# lcd_ex_cap_touch.net
KiCad netlist of a schematic drawn in Altium Designer
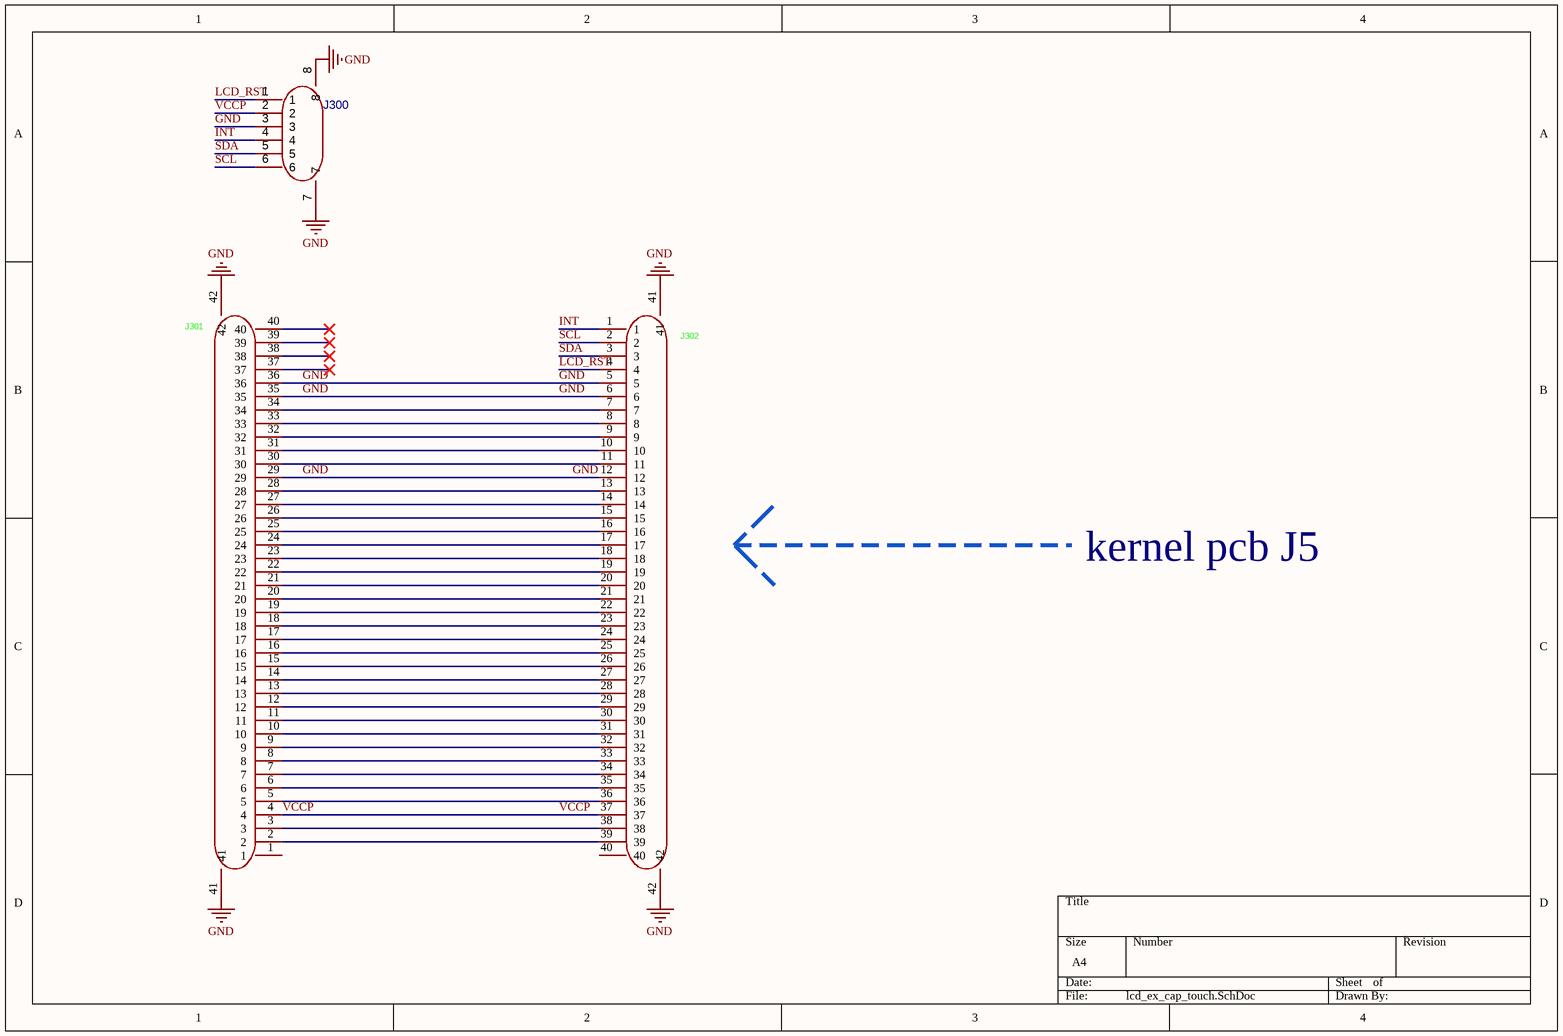
[diagram p0: lcd_ex_cap_touch.SchDoc]

(export (version "E")
  (design (tool "Eeschema 10.0.6"))
  (components
    (comp (ref "J300")
      (value "~")
      (footprint "FPC-SMD_P0.50-6P_QCHF-SM-H2.0_1")
      (libsource (lib "lcd_ex") (part "AFC24-S06FIA-00"))
    )
    (comp (ref "J301")
      (value "AFC01-S40FCA-00")
      (footprint "FPC-SMD_AFC01-S40FCA-00")
      (description "FPC")
      (fields (field (name "MANUFACTURER") "JS(钜硕电子)"))
      (libsource (lib "kernel") (part "AFC01-S40FCA-00"))
    )
    (comp (ref "J302")
      (value "AFC01-S40FCA-00")
      (footprint "FPC-SMD_AFC01-S40FCA-00")
      (description "FPC")
      (fields (field (name "MANUFACTURER") "JS(钜硕电子)"))
      (libsource (lib "kernel") (part "AFC01-S40FCA-00"))
    )
  )
  (nets
    (net (code "1") (name "/INT") (class "Default")
      (node (ref "J300") (pin "4") (pinfunction "4_4") (pintype "passive"))
      (node (ref "J302") (pin "1") (pinfunction "1_1") (pintype "passive"))
    )
    (net (code "2") (name "/LCD_RST") (class "Default")
      (node (ref "J300") (pin "1") (pinfunction "1_1") (pintype "passive"))
      (node (ref "J302") (pin "4") (pinfunction "4_4") (pintype "passive"))
    )
    (net (code "3") (name "/SCL") (class "Default")
      (node (ref "J300") (pin "6") (pinfunction "6_6") (pintype "passive"))
      (node (ref "J302") (pin "2") (pinfunction "2_2") (pintype "passive"))
    )
    (net (code "4") (name "/SDA") (class "Default")
      (node (ref "J300") (pin "5") (pinfunction "5_5") (pintype "passive"))
      (node (ref "J302") (pin "3") (pinfunction "3_3") (pintype "passive"))
    )
    (net (code "5") (name "/VCCP") (class "Default")
      (node (ref "J300") (pin "2") (pinfunction "2_2") (pintype "passive"))
      (node (ref "J301") (pin "4") (pinfunction "4_4") (pintype "passive"))
      (node (ref "J302") (pin "37") (pinfunction "37_37") (pintype "passive"))
    )
    (net (code "6") (name "GND") (class "Default")
      (node (ref "J300") (pin "3") (pinfunction "3_3") (pintype "passive"))
      (node (ref "J300") (pin "7") (pinfunction "7_7") (pintype "passive"))
      (node (ref "J300") (pin "8") (pinfunction "8_8") (pintype "passive"))
      (node (ref "J301") (pin "29") (pinfunction "29_29") (pintype "passive"))
      (node (ref "J301") (pin "35") (pinfunction "35_35") (pintype "passive"))
      (node (ref "J301") (pin "36") (pinfunction "36_36") (pintype "passive"))
      (node (ref "J301") (pin "41") (pinfunction "41_41") (pintype "passive"))
      (node (ref "J301") (pin "42") (pinfunction "42_42") (pintype "passive"))
      (node (ref "J302") (pin "12") (pinfunction "12_12") (pintype "passive"))
      (node (ref "J302") (pin "41") (pinfunction "41_41") (pintype "passive"))
      (node (ref "J302") (pin "42") (pinfunction "42_42") (pintype "passive"))
      (node (ref "J302") (pin "5") (pinfunction "5_5") (pintype "passive"))
      (node (ref "J302") (pin "6") (pinfunction "6_6") (pintype "passive"))
    )
    (net (code "7") (name "Net-(J301-Pad2)") (class "Default")
      (node (ref "J301") (pin "2") (pinfunction "2_2") (pintype "passive"))
      (node (ref "J302") (pin "39") (pinfunction "39_39") (pintype "passive"))
    )
    (net (code "8") (name "Net-(J301-Pad3)") (class "Default")
      (node (ref "J301") (pin "3") (pinfunction "3_3") (pintype "passive"))
      (node (ref "J302") (pin "38") (pinfunction "38_38") (pintype "passive"))
    )
    (net (code "9") (name "Net-(J301-Pad5)") (class "Default")
      (node (ref "J301") (pin "5") (pinfunction "5_5") (pintype "passive"))
      (node (ref "J302") (pin "36") (pinfunction "36_36") (pintype "passive"))
    )
    (net (code "10") (name "Net-(J301-Pad6)") (class "Default")
      (node (ref "J301") (pin "6") (pinfunction "6_6") (pintype "passive"))
      (node (ref "J302") (pin "35") (pinfunction "35_35") (pintype "passive"))
    )
    (net (code "11") (name "Net-(J301-Pad7)") (class "Default")
      (node (ref "J301") (pin "7") (pinfunction "7_7") (pintype "passive"))
      (node (ref "J302") (pin "34") (pinfunction "34_34") (pintype "passive"))
    )
    (net (code "12") (name "Net-(J301-Pad8)") (class "Default")
      (node (ref "J301") (pin "8") (pinfunction "8_8") (pintype "passive"))
      (node (ref "J302") (pin "33") (pinfunction "33_33") (pintype "passive"))
    )
    (net (code "13") (name "Net-(J301-Pad9)") (class "Default")
      (node (ref "J301") (pin "9") (pinfunction "9_9") (pintype "passive"))
      (node (ref "J302") (pin "32") (pinfunction "32_32") (pintype "passive"))
    )
    (net (code "14") (name "Net-(J301-Pad10)") (class "Default")
      (node (ref "J301") (pin "10") (pinfunction "10_10") (pintype "passive"))
      (node (ref "J302") (pin "31") (pinfunction "31_31") (pintype "passive"))
    )
    (net (code "15") (name "Net-(J301-Pad11)") (class "Default")
      (node (ref "J301") (pin "11") (pinfunction "11_11") (pintype "passive"))
      (node (ref "J302") (pin "30") (pinfunction "30_30") (pintype "passive"))
    )
    (net (code "16") (name "Net-(J301-Pad12)") (class "Default")
      (node (ref "J301") (pin "12") (pinfunction "12_12") (pintype "passive"))
      (node (ref "J302") (pin "29") (pinfunction "29_29") (pintype "passive"))
    )
    (net (code "17") (name "Net-(J301-Pad13)") (class "Default")
      (node (ref "J301") (pin "13") (pinfunction "13_13") (pintype "passive"))
      (node (ref "J302") (pin "28") (pinfunction "28_28") (pintype "passive"))
    )
    (net (code "18") (name "Net-(J301-Pad14)") (class "Default")
      (node (ref "J301") (pin "14") (pinfunction "14_14") (pintype "passive"))
      (node (ref "J302") (pin "27") (pinfunction "27_27") (pintype "passive"))
    )
    (net (code "19") (name "Net-(J301-Pad15)") (class "Default")
      (node (ref "J301") (pin "15") (pinfunction "15_15") (pintype "passive"))
      (node (ref "J302") (pin "26") (pinfunction "26_26") (pintype "passive"))
    )
    (net (code "20") (name "Net-(J301-Pad16)") (class "Default")
      (node (ref "J301") (pin "16") (pinfunction "16_16") (pintype "passive"))
      (node (ref "J302") (pin "25") (pinfunction "25_25") (pintype "passive"))
    )
    (net (code "21") (name "Net-(J301-Pad17)") (class "Default")
      (node (ref "J301") (pin "17") (pinfunction "17_17") (pintype "passive"))
      (node (ref "J302") (pin "24") (pinfunction "24_24") (pintype "passive"))
    )
    (net (code "22") (name "Net-(J301-Pad18)") (class "Default")
      (node (ref "J301") (pin "18") (pinfunction "18_18") (pintype "passive"))
      (node (ref "J302") (pin "23") (pinfunction "23_23") (pintype "passive"))
    )
    (net (code "23") (name "Net-(J301-Pad19)") (class "Default")
      (node (ref "J301") (pin "19") (pinfunction "19_19") (pintype "passive"))
      (node (ref "J302") (pin "22") (pinfunction "22_22") (pintype "passive"))
    )
    (net (code "24") (name "Net-(J301-Pad20)") (class "Default")
      (node (ref "J301") (pin "20") (pinfunction "20_20") (pintype "passive"))
      (node (ref "J302") (pin "21") (pinfunction "21_21") (pintype "passive"))
    )
    (net (code "25") (name "Net-(J301-Pad21)") (class "Default")
      (node (ref "J301") (pin "21") (pinfunction "21_21") (pintype "passive"))
      (node (ref "J302") (pin "20") (pinfunction "20_20") (pintype "passive"))
    )
    (net (code "26") (name "Net-(J301-Pad22)") (class "Default")
      (node (ref "J301") (pin "22") (pinfunction "22_22") (pintype "passive"))
      (node (ref "J302") (pin "19") (pinfunction "19_19") (pintype "passive"))
    )
    (net (code "27") (name "Net-(J301-Pad23)") (class "Default")
      (node (ref "J301") (pin "23") (pinfunction "23_23") (pintype "passive"))
      (node (ref "J302") (pin "18") (pinfunction "18_18") (pintype "passive"))
    )
    (net (code "28") (name "Net-(J301-Pad24)") (class "Default")
      (node (ref "J301") (pin "24") (pinfunction "24_24") (pintype "passive"))
      (node (ref "J302") (pin "17") (pinfunction "17_17") (pintype "passive"))
    )
    (net (code "29") (name "Net-(J301-Pad25)") (class "Default")
      (node (ref "J301") (pin "25") (pinfunction "25_25") (pintype "passive"))
      (node (ref "J302") (pin "16") (pinfunction "16_16") (pintype "passive"))
    )
    (net (code "30") (name "Net-(J301-Pad26)") (class "Default")
      (node (ref "J301") (pin "26") (pinfunction "26_26") (pintype "passive"))
      (node (ref "J302") (pin "15") (pinfunction "15_15") (pintype "passive"))
    )
    (net (code "31") (name "Net-(J301-Pad27)") (class "Default")
      (node (ref "J301") (pin "27") (pinfunction "27_27") (pintype "passive"))
      (node (ref "J302") (pin "14") (pinfunction "14_14") (pintype "passive"))
    )
    (net (code "32") (name "Net-(J301-Pad28)") (class "Default")
      (node (ref "J301") (pin "28") (pinfunction "28_28") (pintype "passive"))
      (node (ref "J302") (pin "13") (pinfunction "13_13") (pintype "passive"))
    )
    (net (code "33") (name "Net-(J301-Pad30)") (class "Default")
      (node (ref "J301") (pin "30") (pinfunction "30_30") (pintype "passive"))
      (node (ref "J302") (pin "11") (pinfunction "11_11") (pintype "passive"))
    )
    (net (code "34") (name "Net-(J301-Pad31)") (class "Default")
      (node (ref "J301") (pin "31") (pinfunction "31_31") (pintype "passive"))
      (node (ref "J302") (pin "10") (pinfunction "10_10") (pintype "passive"))
    )
    (net (code "35") (name "Net-(J301-Pad32)") (class "Default")
      (node (ref "J301") (pin "32") (pinfunction "32_32") (pintype "passive"))
      (node (ref "J302") (pin "9") (pinfunction "9_9") (pintype "passive"))
    )
    (net (code "36") (name "Net-(J301-Pad33)") (class "Default")
      (node (ref "J301") (pin "33") (pinfunction "33_33") (pintype "passive"))
      (node (ref "J302") (pin "8") (pinfunction "8_8") (pintype "passive"))
    )
    (net (code "37") (name "Net-(J301-Pad34)") (class "Default")
      (node (ref "J301") (pin "34") (pinfunction "34_34") (pintype "passive"))
      (node (ref "J302") (pin "7") (pinfunction "7_7") (pintype "passive"))
    )
    (net (code "38") (name "unconnected-(J301-Pad1)") (class "Default")
      (node (ref "J301") (pin "1") (pinfunction "1_1") (pintype "passive"))
    )
    (net (code "39") (name "unconnected-(J301-Pad37)") (class "Default")
      (node (ref "J301") (pin "37") (pinfunction "37_37") (pintype "passive+no_connect"))
    )
    (net (code "40") (name "unconnected-(J301-Pad38)") (class "Default")
      (node (ref "J301") (pin "38") (pinfunction "38_38") (pintype "passive+no_connect"))
    )
    (net (code "41") (name "unconnected-(J301-Pad39)") (class "Default")
      (node (ref "J301") (pin "39") (pinfunction "39_39") (pintype "passive+no_connect"))
    )
    (net (code "42") (name "unconnected-(J301-Pad40)") (class "Default")
      (node (ref "J301") (pin "40") (pinfunction "40_40") (pintype "passive+no_connect"))
    )
    (net (code "43") (name "unconnected-(J302-Pad40)") (class "Default")
      (node (ref "J302") (pin "40") (pinfunction "40_40") (pintype "passive"))
    )
  )
)
